# 07_Programming_Reset.net
KiCad netlist of a schematic drawn in Altium Designer
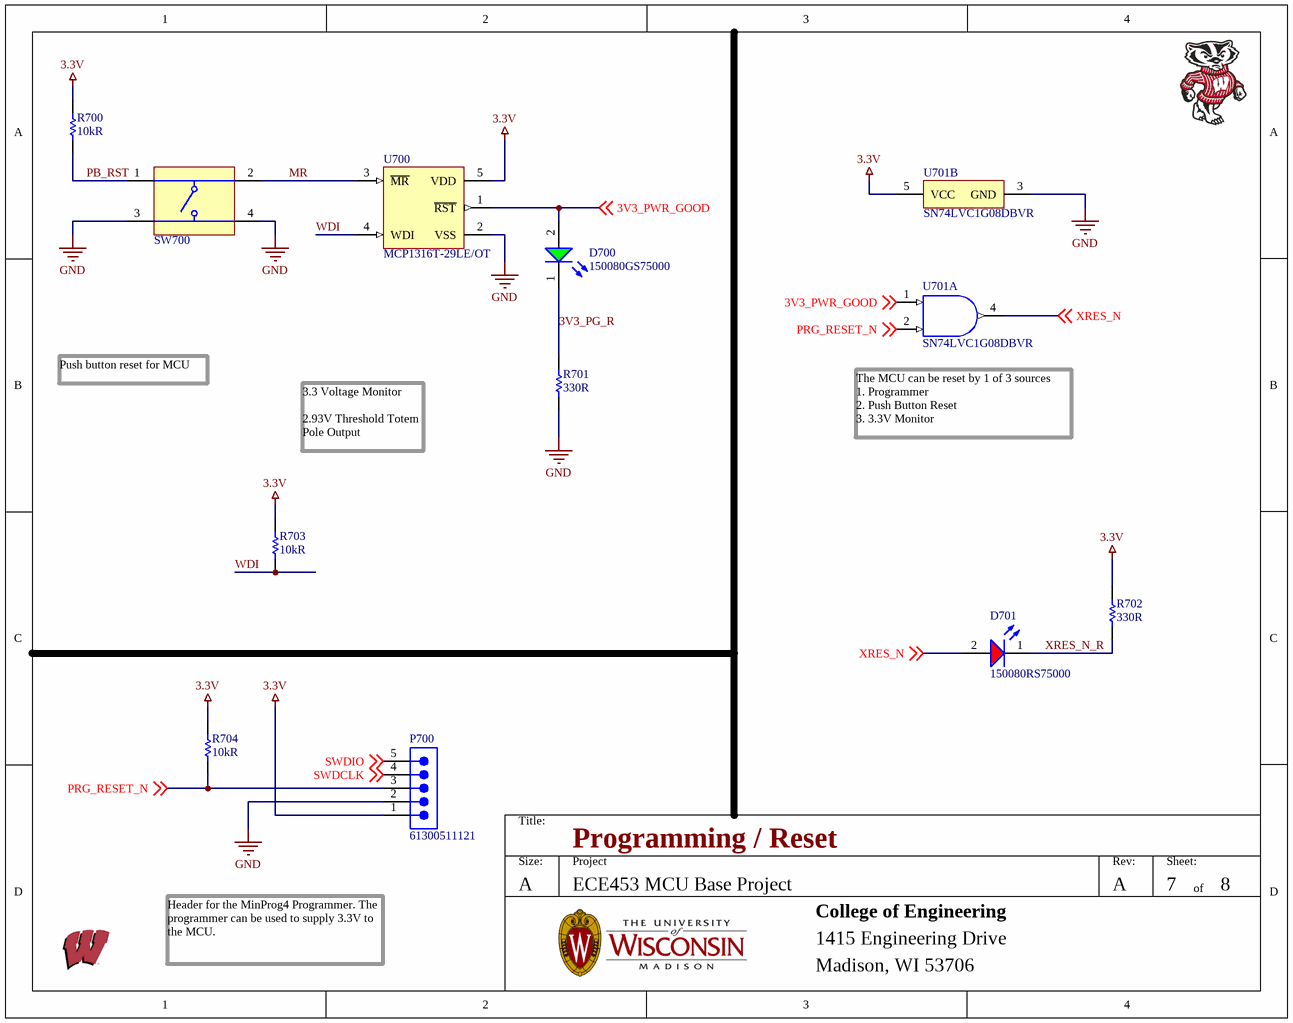
[diagram p0: 07_Programming_Reset.SchDoc]

(export (version "E")
  (design (tool "Eeschema 10.0.6"))
  (components
    (comp (ref "D700")
      (value "150080GS75000")
      (footprint "WL-SMCW_0805_150080xx75000")
      (libsource (lib "Altium Content Vault") (part "LED_Green_2A-1K"))
    )
    (comp (ref "D701")
      (value "150080RS75000")
      (footprint "WL-SMCW_0805_150080xx75000")
      (libsource (lib "Altium Content Vault") (part "LED_Red_2A-1K"))
    )
    (comp (ref "P700")
      (value "61300511121")
      (footprint "61300511121")
      (libsource (lib "Altium Content Vault") (part "Header_Male_1R_05P"))
    )
    (comp (ref "R700")
      (value "10kR")
      (footprint "RESC2013X70X40ML20T20")
      (fields (field (name "MANUFACTURER") "Panasonic") (field (name "PART NUMBER") "ERJ-6ENF1002V"))
      (libsource (lib "Altium Content Vault") (part "RES"))
    )
    (comp (ref "R701")
      (value "330R")
      (footprint "RESC2013X60X40LL20T25")
      (fields (field (name "MANUFACTURER") "Panasonic") (field (name "PART NUMBER") "ERA6AEB331V"))
      (libsource (lib "Altium Content Vault") (part "RES"))
    )
    (comp (ref "R702")
      (value "330R")
      (footprint "RESC2013X60X40LL20T25")
      (fields (field (name "MANUFACTURER") "Panasonic") (field (name "PART NUMBER") "ERA6AEB331V"))
      (libsource (lib "Altium Content Vault") (part "RES"))
    )
    (comp (ref "R703")
      (value "10kR")
      (footprint "RESC2013X70X40ML20T20")
      (fields (field (name "MANUFACTURER") "Panasonic") (field (name "PART NUMBER") "ERJ-6ENF1002V"))
      (libsource (lib "Altium Content Vault") (part "RES"))
    )
    (comp (ref "R704")
      (value "10kR")
      (footprint "RESC2013X70X40ML20T20")
      (fields (field (name "MANUFACTURER") "Panasonic") (field (name "PART NUMBER") "ERJ-6ENF1002V"))
      (libsource (lib "Altium Content Vault") (part "RES"))
    )
    (comp (ref "SW700")
      (value "~")
      (footprint "TECO-FSM4JSMA_V")
      (description "Swicth, SPST, 24 V, -35 to 85 degC, 4-Pin SMD, RoHS, Tape and Reel")
      (fields (field (name "MANUFACTURER") "TE Connectivity"))
      (libsource (lib "Altium Content Vault") (part "SW-SPST-4_A"))
    )
    (comp (ref "U700")
      (value "MCP1316T-29LE/OT")
      (footprint "SOT-23-OT5_M")
      (description "Voltage Supervisor, 5-Pin SOT-23, Extended Temperature, Tape and Reel")
      (libsource (lib "Altium Content Vault") (part "PM-SCCT-MCP1316-5"))
    )
    (comp (ref "U701")
      (value "SN74LVC1G08DBVR")
      (footprint "DBV0005A_M")
      (description "Single 2-Input Positive-AND Gate, DBV0005A, LARGE T&R")
      (fields
        (field (name "GENERIC PART NUMBER") "SN74LVC1G08")
        (field (name "MANUFACTURER") "Texas Instruments")
      )
      (libsource (lib "Altium Content Vault") (part "TI-SN74XXX1X08-5"))
    )
  )
  (nets
    (net (code "1") (name "/3V3_PG_R") (class "Default")
      (node (ref "D700") (pin "1") (pinfunction "K_1") (pintype "passive"))
      (node (ref "R701") (pin "1") (pinfunction "1_1") (pintype "passive"))
    )
    (net (code "2") (name "/MR") (class "Default")
      (node (ref "SW700") (pin "2") (pinfunction "2_2") (pintype "passive"))
      (node (ref "U700") (pin "3") (pinfunction "~{MR}_3") (pintype "input"))
    )
    (net (code "3") (name "/PB_RST") (class "Default")
      (node (ref "R700") (pin "1") (pinfunction "1_1") (pintype "passive"))
      (node (ref "SW700") (pin "1") (pinfunction "1_1") (pintype "passive"))
    )
    (net (code "4") (name "/WDI") (class "Default")
      (node (ref "R703") (pin "1") (pinfunction "1_1") (pintype "passive"))
      (node (ref "U700") (pin "4") (pinfunction "WDI_4") (pintype "input"))
    )
    (net (code "5") (name "/XRES_N_R") (class "Default")
      (node (ref "D701") (pin "1") (pinfunction "K_1") (pintype "passive"))
      (node (ref "R702") (pin "2") (pinfunction "2_2") (pintype "passive"))
    )
    (net (code "6") (name "3.3V") (class "Default")
      (node (ref "P700") (pin "1") (pinfunction "1_1") (pintype "passive"))
      (node (ref "R700") (pin "2") (pinfunction "2_2") (pintype "passive"))
      (node (ref "R702") (pin "1") (pinfunction "1_1") (pintype "passive"))
      (node (ref "R703") (pin "2") (pinfunction "2_2") (pintype "passive"))
      (node (ref "R704") (pin "2") (pinfunction "2_2") (pintype "passive"))
      (node (ref "U700") (pin "5") (pinfunction "VDD_5") (pintype "power_in"))
      (node (ref "U701") (pin "5") (pinfunction "VCC_5") (pintype "power_in"))
    )
    (net (code "7") (name "3V3_PWR_GOOD") (class "Default")
      (node (ref "D700") (pin "2") (pinfunction "A_2") (pintype "passive"))
      (node (ref "U700") (pin "1") (pinfunction "~{RST}_1") (pintype "output"))
      (node (ref "U701") (pin "1") (pinfunction "A_1") (pintype "input"))
    )
    (net (code "8") (name "GND") (class "Default")
      (node (ref "P700") (pin "2") (pinfunction "2_2") (pintype "passive"))
      (node (ref "R701") (pin "2") (pinfunction "2_2") (pintype "passive"))
      (node (ref "SW700") (pin "3") (pinfunction "3_3") (pintype "passive"))
      (node (ref "SW700") (pin "4") (pinfunction "4_4") (pintype "passive"))
      (node (ref "U700") (pin "2") (pinfunction "VSS_2") (pintype "power_in"))
      (node (ref "U701") (pin "3") (pinfunction "GND_3") (pintype "power_in"))
    )
    (net (code "9") (name "PRG_RESET_N") (class "Default")
      (node (ref "P700") (pin "3") (pinfunction "3_3") (pintype "passive"))
      (node (ref "R704") (pin "1") (pinfunction "1_1") (pintype "passive"))
      (node (ref "U701") (pin "2") (pinfunction "B_2") (pintype "input"))
    )
    (net (code "10") (name "SWDCLK") (class "Default")
      (node (ref "P700") (pin "4") (pinfunction "4_4") (pintype "passive"))
    )
    (net (code "11") (name "SWDIO") (class "Default")
      (node (ref "P700") (pin "5") (pinfunction "5_5") (pintype "passive"))
    )
    (net (code "12") (name "XRES_N") (class "Default")
      (node (ref "D701") (pin "2") (pinfunction "A_2") (pintype "passive"))
      (node (ref "U701") (pin "4") (pinfunction "Y_4") (pintype "output"))
    )
  )
)
